# ESP32_LoRa_1_Channel_Gateway.net
KiCad netlist of a schematic drawn in EAGLE
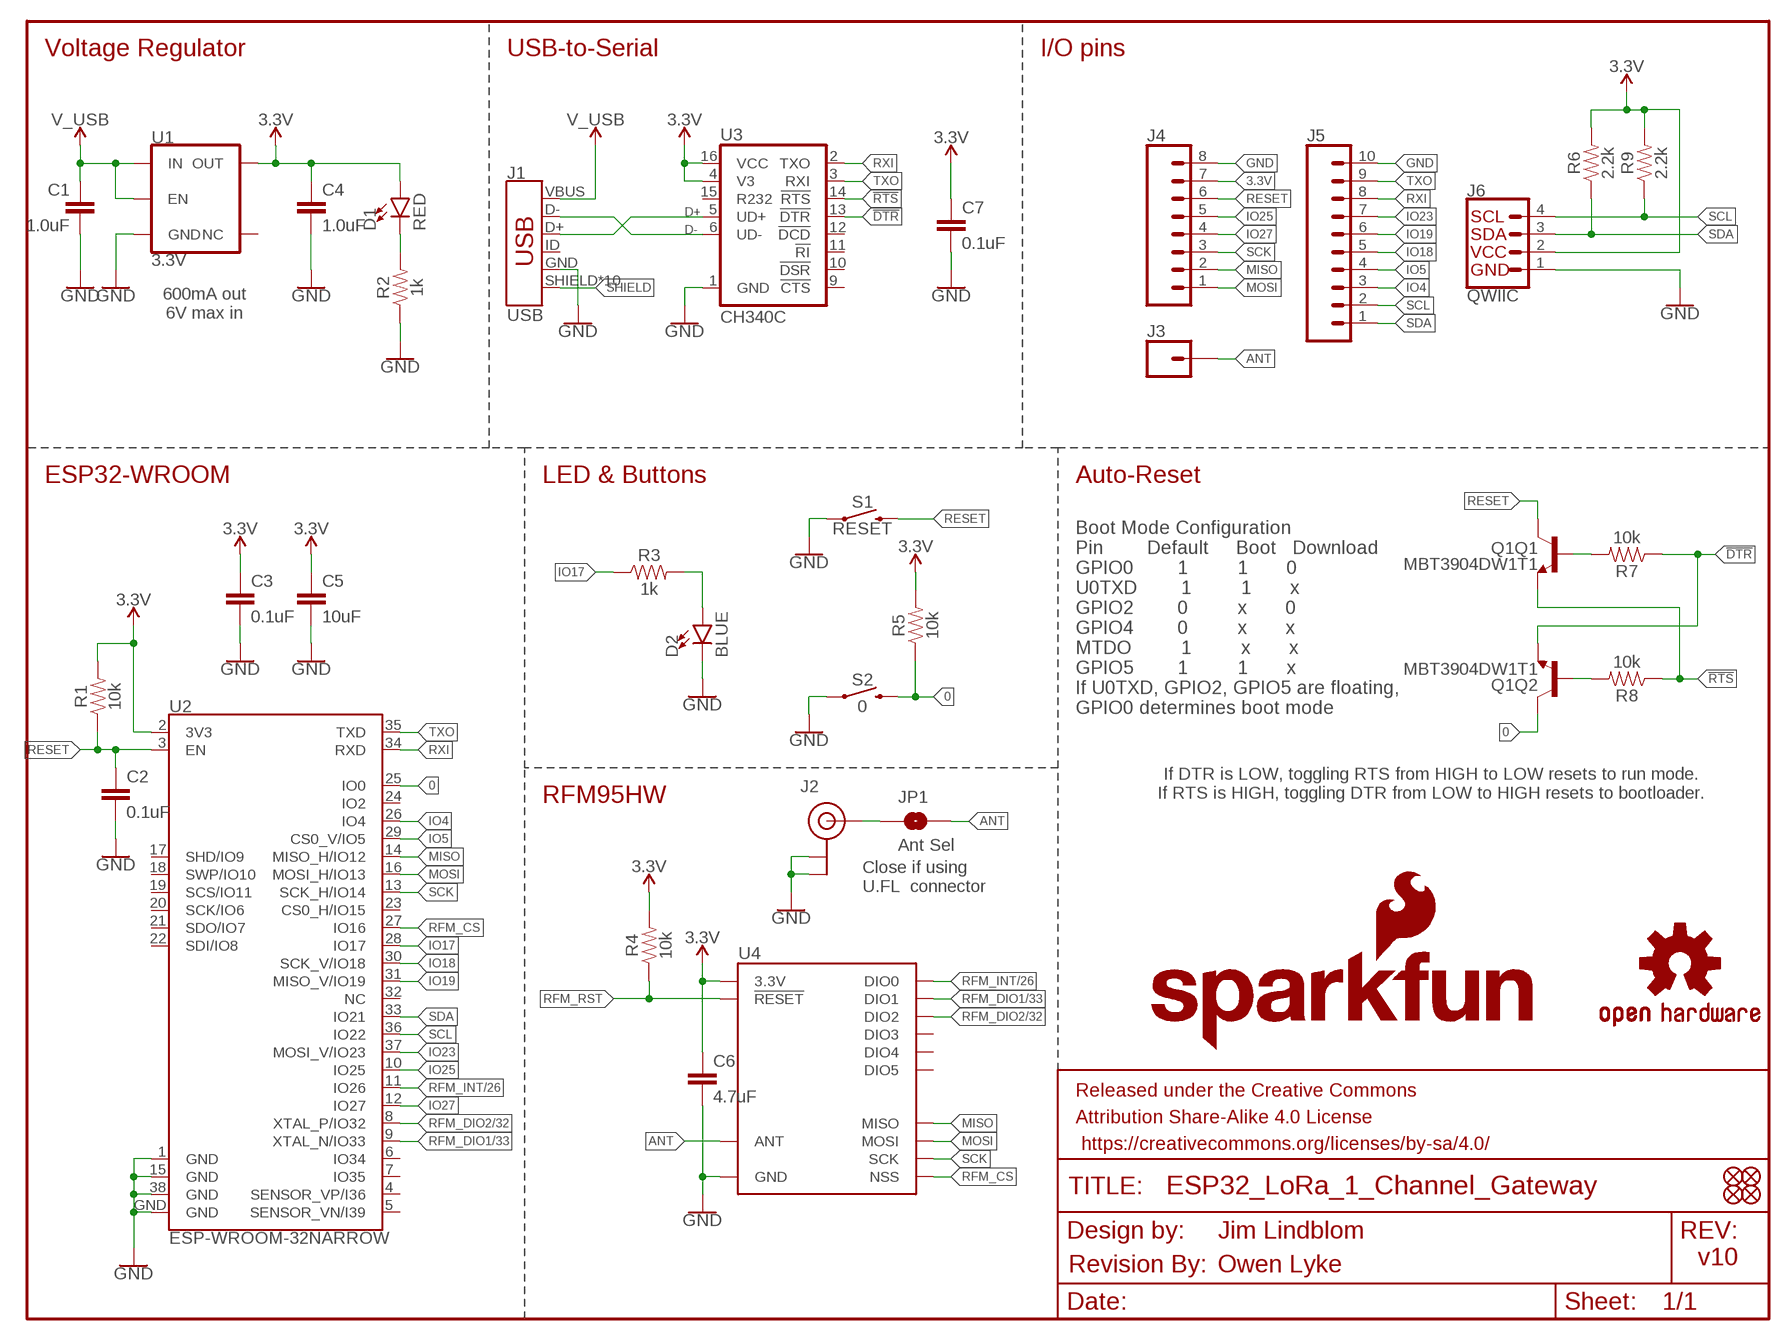
[diagram p0: schematic, sheet 1]

(export (version "E")
  (design (tool "Eeschema 10.0.6"))
  (components
    (comp (ref "C1")
      (value "1.0uF")
      (footprint "eagle-import:0603")
      (libsource (lib "eagle-import") (part "1.0UF-0603-16V-10%"))
    )
    (comp (ref "C2")
      (value "0.1uF")
      (footprint "eagle-import:0603")
      (libsource (lib "eagle-import") (part "0.1UF-0603-25V-(+80/-20%)"))
    )
    (comp (ref "C3")
      (value "0.1uF")
      (footprint "eagle-import:0603")
      (libsource (lib "eagle-import") (part "0.1UF-0603-25V-(+80/-20%)"))
    )
    (comp (ref "C4")
      (value "1.0uF")
      (footprint "eagle-import:0603")
      (libsource (lib "eagle-import") (part "1.0UF-0603-16V-10%"))
    )
    (comp (ref "C5")
      (value "10uF")
      (footprint "eagle-import:0603")
      (libsource (lib "eagle-import") (part "10UF-0603-6.3V-20%"))
    )
    (comp (ref "C6")
      (value "4.7uF")
      (footprint "eagle-import:0603")
      (libsource (lib "eagle-import") (part "4.7UF-0603-6.3V-(10%)"))
    )
    (comp (ref "C7")
      (value "0.1uF")
      (footprint "eagle-import:0603")
      (libsource (lib "eagle-import") (part "0.1UF-0603-25V-5%"))
    )
    (comp (ref "D1")
      (value "RED")
      (footprint "eagle-import:LED-0603")
      (libsource (lib "eagle-import") (part "LED-RED0603"))
    )
    (comp (ref "D2")
      (value "BLUE")
      (footprint "eagle-import:LED-0603")
      (libsource (lib "eagle-import") (part "LED-BLUE0603"))
    )
    (comp (ref "FD1")
      (value "FIDUCIAL1X2")
      (footprint "eagle-import:FIDUCIAL-1X2")
      (libsource (lib "eagle-import") (part "FIDUCIAL1X2"))
    )
    (comp (ref "FD2")
      (value "FIDUCIAL1X2")
      (footprint "eagle-import:FIDUCIAL-1X2")
      (libsource (lib "eagle-import") (part "FIDUCIAL1X2"))
    )
    (comp (ref "FD3")
      (value "FIDUCIAL1X2")
      (footprint "eagle-import:FIDUCIAL-1X2")
      (libsource (lib "eagle-import") (part "FIDUCIAL1X2"))
    )
    (comp (ref "FD4")
      (value "FIDUCIAL1X2")
      (footprint "eagle-import:FIDUCIAL-1X2")
      (libsource (lib "eagle-import") (part "FIDUCIAL1X2"))
    )
    (comp (ref "FRAME1")
      (value "FRAME-LETTER")
      (footprint "eagle-import:CREATIVE_COMMONS")
      (libsource (lib "eagle-import") (part "FRAME-LETTER"))
    )
    (comp (ref "J1")
      (value "USB")
      (footprint "eagle-import:USB-MICROB-PTH-MILL")
      (libsource (lib "eagle-import") (part "USB_MICRO-B_HALF_PTH_MILL"))
    )
    (comp (ref "J2")
      (value "U.FL")
      (footprint "eagle-import:U.FL")
      (libsource (lib "eagle-import") (part "U.FL"))
    )
    (comp (ref "J3")
      (value "CONN_01PTH_NO_SILK_YES_STOP")
      (footprint "eagle-import:1X01_NO_SILK")
      (libsource (lib "eagle-import") (part "CONN_01PTH_NO_SILK_YES_STOP"))
    )
    (comp (ref "J4")
      (value "CONN_08NO_SILK_FEMALE_PTH")
      (footprint "eagle-import:1X08_NO_SILK")
      (libsource (lib "eagle-import") (part "CONN_08NO_SILK_FEMALE_PTH"))
    )
    (comp (ref "J5")
      (value "CONN_10NO_SILK_PTH_FEMALE")
      (footprint "eagle-import:1X10_NO_SILK")
      (libsource (lib "eagle-import") (part "CONN_10NO_SILK_PTH_FEMALE"))
    )
    (comp (ref "J6")
      (value "QWIIC")
      (footprint "eagle-import:1X04_1MM_RA")
      (libsource (lib "eagle-import") (part "QWIIC_CONNECTORJS-1MM"))
    )
    (comp (ref "JP1")
      (value "Ant Sel")
      (footprint "eagle-import:SMT-JUMPER_2_NO_NO-SILK")
      (libsource (lib "eagle-import") (part "JUMPER-SMT_2_NO_NO-SILK"))
    )
    (comp (ref "LOGO1")
      (value "REVISION")
      (footprint "eagle-import:REVISION")
      (libsource (lib "eagle-import") (part "REVISION"))
    )
    (comp (ref "LOGO2")
      (value "SFE_LOGO_NAME_FLAME.1_INCH")
      (footprint "eagle-import:SFE_LOGO_NAME_FLAME_.1")
      (libsource (lib "eagle-import") (part "SFE_LOGO_NAME_FLAME.1_INCH"))
    )
    (comp (ref "LOGO3")
      (value "OSHW-LOGOS")
      (footprint "eagle-import:OSHW-LOGO-S")
      (libsource (lib "eagle-import") (part "OSHW-LOGOS"))
    )
    (comp (ref "Q1")
      (value "MBT3904DW1T1")
      (footprint "eagle-import:SC70-6")
      (libsource (lib "eagle-import") (part "TRANS_NPN_DUAL-MBT3904DW1T1"))
    )
    (comp (ref "R1")
      (value "10k")
      (footprint "eagle-import:0603")
      (libsource (lib "eagle-import") (part "10KOHM-0603-1/10W-1%"))
    )
    (comp (ref "R2")
      (value "1k")
      (footprint "eagle-import:0603")
      (libsource (lib "eagle-import") (part "1KOHM-0603-1/10W-1%"))
    )
    (comp (ref "R3")
      (value "1k")
      (footprint "eagle-import:0603")
      (libsource (lib "eagle-import") (part "1KOHM-0603-1/10W-1%"))
    )
    (comp (ref "R4")
      (value "10k")
      (footprint "eagle-import:0603")
      (libsource (lib "eagle-import") (part "10KOHM-0603-1/10W-1%"))
    )
    (comp (ref "R5")
      (value "10k")
      (footprint "eagle-import:0603")
      (libsource (lib "eagle-import") (part "10KOHM-0603-1/10W-1%"))
    )
    (comp (ref "R6")
      (value "2.2k")
      (footprint "eagle-import:0603")
      (libsource (lib "eagle-import") (part "2.2KOHM-0603-1/10W-1%"))
    )
    (comp (ref "R7")
      (value "10k")
      (footprint "eagle-import:0603")
      (libsource (lib "eagle-import") (part "10KOHM-0603-1/10W-1%"))
    )
    (comp (ref "R8")
      (value "10k")
      (footprint "eagle-import:0603")
      (libsource (lib "eagle-import") (part "10KOHM-0603-1/10W-1%"))
    )
    (comp (ref "R9")
      (value "2.2k")
      (footprint "eagle-import:0603")
      (libsource (lib "eagle-import") (part "2.2KOHM-0603-1/10W-1%"))
    )
    (comp (ref "S1")
      (value "RESET")
      (footprint "eagle-import:TACTILE_SWITCH_SMD_4.6X2.8MM")
      (libsource (lib "eagle-import") (part "MOMENTARY-SWITCH-SPST-SMD-4.6X2.8MM"))
    )
    (comp (ref "S2")
      (value "0")
      (footprint "eagle-import:TACTILE_SWITCH_SMD_4.6X2.8MM")
      (libsource (lib "eagle-import") (part "MOMENTARY-SWITCH-SPST-SMD-4.6X2.8MM"))
    )
    (comp (ref "U1")
      (value "3.3V")
      (footprint "eagle-import:SOT23-5")
      (libsource (lib "eagle-import") (part "V_REG_AP2112K-3.3V"))
    )
    (comp (ref "U2")
      (value "ESP-WROOM-32NARROW")
      (footprint "eagle-import:ESP-WROOM-32-NARROW")
      (libsource (lib "eagle-import") (part "ESP-WROOM-32NARROW"))
    )
    (comp (ref "U3")
      (value "CH340C")
      (footprint "eagle-import:SO016")
      (libsource (lib "eagle-import") (part "CH340C"))
    )
    (comp (ref "U4")
      (value "RFM95W")
      (footprint "eagle-import:RFM95_96_97_98W")
      (libsource (lib "eagle-import") (part "RFM95W"))
    )
  )
  (nets
    (net (code "1") (name "/D+") (class "Default")
      (node (ref "J1") (pin "D+") (pinfunction "D+_D+") (pintype "bidirectional"))
      (node (ref "U3") (pin "5") (pinfunction "UD+_5") (pintype "bidirectional"))
    )
    (net (code "2") (name "/D-") (class "Default")
      (node (ref "J1") (pin "D-") (pinfunction "D-_D-") (pintype "bidirectional"))
      (node (ref "U3") (pin "6") (pinfunction "UD-_6") (pintype "bidirectional"))
    )
    (net (code "3") (name "/~{DTR}") (class "Default")
      (node (ref "Q1") (pin "1") (pinfunction "E_1") (pintype "passive"))
      (node (ref "R7") (pin "1") (pinfunction "1_1") (pintype "passive"))
      (node (ref "U3") (pin "13") (pinfunction "~{DTR}_13") (pintype "bidirectional"))
    )
    (net (code "4") (name "/~{RTS}") (class "Default")
      (node (ref "Q1") (pin "4") (pinfunction "E_4") (pintype "passive"))
      (node (ref "R8") (pin "1") (pinfunction "1_1") (pintype "passive"))
      (node (ref "U3") (pin "14") (pinfunction "~{RTS}_14") (pintype "bidirectional"))
    )
    (net (code "5") (name "0") (class "Default")
      (node (ref "Q1") (pin "6") (pinfunction "C_6") (pintype "passive"))
      (node (ref "R5") (pin "1") (pinfunction "1_1") (pintype "passive"))
      (node (ref "S2") (pin "3") (pinfunction "2_3") (pintype "passive"))
      (node (ref "S2") (pin "4") (pinfunction "2_4") (pintype "passive"))
      (node (ref "U2") (pin "25") (pinfunction "IO0_25") (pintype "bidirectional"))
    )
    (net (code "6") (name "3.3V") (class "Default")
      (node (ref "C3") (pin "1") (pinfunction "1_1") (pintype "passive"))
      (node (ref "C4") (pin "1") (pinfunction "1_1") (pintype "passive"))
      (node (ref "C5") (pin "1") (pinfunction "1_1") (pintype "passive"))
      (node (ref "C6") (pin "1") (pinfunction "1_1") (pintype "passive"))
      (node (ref "C7") (pin "1") (pinfunction "1_1") (pintype "passive"))
      (node (ref "D1") (pin "A") (pinfunction "A_A") (pintype "passive"))
      (node (ref "J4") (pin "7") (pinfunction "7_7") (pintype "passive"))
      (node (ref "J6") (pin "2") (pinfunction "2_2") (pintype "power_in"))
      (node (ref "R1") (pin "2") (pinfunction "2_2") (pintype "passive"))
      (node (ref "R4") (pin "2") (pinfunction "2_2") (pintype "passive"))
      (node (ref "R5") (pin "2") (pinfunction "2_2") (pintype "passive"))
      (node (ref "R6") (pin "2") (pinfunction "2_2") (pintype "passive"))
      (node (ref "R9") (pin "2") (pinfunction "2_2") (pintype "passive"))
      (node (ref "U1") (pin "5") (pinfunction "OUT_5") (pintype "passive"))
      (node (ref "U2") (pin "2") (pinfunction "3V3_2") (pintype "bidirectional"))
      (node (ref "U3") (pin "16") (pinfunction "VCC_16") (pintype "bidirectional"))
      (node (ref "U3") (pin "4") (pinfunction "V3_4") (pintype "bidirectional"))
      (node (ref "U4") (pin "3.3V") (pinfunction "3.3V_3.3V") (pintype "bidirectional"))
    )
    (net (code "7") (name "ANT") (class "Default")
      (node (ref "J3") (pin "1") (pinfunction "1_1") (pintype "passive"))
      (node (ref "JP1") (pin "2") (pinfunction "2_2") (pintype "passive"))
      (node (ref "U4") (pin "ANT") (pinfunction "ANT_ANT") (pintype "bidirectional"))
    )
    (net (code "8") (name "GND") (class "Default")
      (node (ref "C1") (pin "2") (pinfunction "2_2") (pintype "passive"))
      (node (ref "C2") (pin "2") (pinfunction "2_2") (pintype "passive"))
      (node (ref "C3") (pin "2") (pinfunction "2_2") (pintype "passive"))
      (node (ref "C4") (pin "2") (pinfunction "2_2") (pintype "passive"))
      (node (ref "C5") (pin "2") (pinfunction "2_2") (pintype "passive"))
      (node (ref "C6") (pin "2") (pinfunction "2_2") (pintype "passive"))
      (node (ref "C7") (pin "2") (pinfunction "2_2") (pintype "passive"))
      (node (ref "D2") (pin "C") (pinfunction "C_C") (pintype "passive"))
      (node (ref "J1") (pin "GND") (pinfunction "GND_GND") (pintype "power_in"))
      (node (ref "J2") (pin "1") (pinfunction "GND_1") (pintype "bidirectional"))
      (node (ref "J2") (pin "2") (pinfunction "GND_2") (pintype "bidirectional"))
      (node (ref "J4") (pin "8") (pinfunction "8_8") (pintype "passive"))
      (node (ref "J5") (pin "10") (pinfunction "10_10") (pintype "passive"))
      (node (ref "J6") (pin "1") (pinfunction "1_1") (pintype "power_in"))
      (node (ref "R2") (pin "1") (pinfunction "1_1") (pintype "passive"))
      (node (ref "S1") (pin "1") (pinfunction "1_1") (pintype "passive"))
      (node (ref "S1") (pin "2") (pinfunction "1_2") (pintype "passive"))
      (node (ref "S2") (pin "1") (pinfunction "1_1") (pintype "passive"))
      (node (ref "S2") (pin "2") (pinfunction "1_2") (pintype "passive"))
      (node (ref "U1") (pin "2") (pinfunction "GND_2") (pintype "input"))
      (node (ref "U2") (pin "1") (pinfunction "GND_1") (pintype "bidirectional"))
      (node (ref "U2") (pin "15") (pinfunction "GND_15") (pintype "bidirectional"))
      (node (ref "U2") (pin "38") (pinfunction "GND_38") (pintype "bidirectional"))
      (node (ref "U2") (pin "GND") (pinfunction "GND_GND") (pintype "bidirectional"))
      (node (ref "U3") (pin "1") (pinfunction "GND_1") (pintype "bidirectional"))
      (node (ref "U4") (pin "GND@1") (pinfunction "GND_GND@1") (pintype "bidirectional"))
      (node (ref "U4") (pin "GND@2") (pinfunction "GND_GND@2") (pintype "bidirectional"))
      (node (ref "U4") (pin "GND@3") (pinfunction "GND_GND@3") (pintype "bidirectional"))
    )
    (net (code "9") (name "IO4") (class "Default")
      (node (ref "J5") (pin "3") (pinfunction "3_3") (pintype "passive"))
      (node (ref "U2") (pin "26") (pinfunction "IO4_26") (pintype "bidirectional"))
    )
    (net (code "10") (name "IO5") (class "Default")
      (node (ref "J5") (pin "4") (pinfunction "4_4") (pintype "passive"))
      (node (ref "U2") (pin "29") (pinfunction "CS0_V/IO5_29") (pintype "bidirectional"))
    )
    (net (code "11") (name "IO17") (class "Default")
      (node (ref "R3") (pin "1") (pinfunction "1_1") (pintype "passive"))
      (node (ref "U2") (pin "28") (pinfunction "IO17_28") (pintype "bidirectional"))
    )
    (net (code "12") (name "IO18") (class "Default")
      (node (ref "J5") (pin "5") (pinfunction "5_5") (pintype "passive"))
      (node (ref "U2") (pin "30") (pinfunction "SCK_V/IO18_30") (pintype "bidirectional"))
    )
    (net (code "13") (name "IO19") (class "Default")
      (node (ref "J5") (pin "6") (pinfunction "6_6") (pintype "passive"))
      (node (ref "U2") (pin "31") (pinfunction "MISO_V/IO19_31") (pintype "bidirectional"))
    )
    (net (code "14") (name "IO23") (class "Default")
      (node (ref "J5") (pin "7") (pinfunction "7_7") (pintype "passive"))
      (node (ref "U2") (pin "37") (pinfunction "MOSI_V/IO23_37") (pintype "bidirectional"))
    )
    (net (code "15") (name "IO25") (class "Default")
      (node (ref "J4") (pin "5") (pinfunction "5_5") (pintype "passive"))
      (node (ref "U2") (pin "10") (pinfunction "IO25_10") (pintype "bidirectional"))
    )
    (net (code "16") (name "IO27") (class "Default")
      (node (ref "J4") (pin "4") (pinfunction "4_4") (pintype "passive"))
      (node (ref "U2") (pin "12") (pinfunction "IO27_12") (pintype "bidirectional"))
    )
    (net (code "17") (name "MISO") (class "Default")
      (node (ref "J4") (pin "2") (pinfunction "2_2") (pintype "passive"))
      (node (ref "U2") (pin "14") (pinfunction "MISO_H/IO12_14") (pintype "bidirectional"))
      (node (ref "U4") (pin "MISO") (pinfunction "MISO_MISO") (pintype "bidirectional"))
    )
    (net (code "18") (name "MOSI") (class "Default")
      (node (ref "J4") (pin "1") (pinfunction "1_1") (pintype "passive"))
      (node (ref "U2") (pin "16") (pinfunction "MOSI_H/IO13_16") (pintype "bidirectional"))
      (node (ref "U4") (pin "MOSI") (pinfunction "MOSI_MOSI") (pintype "bidirectional"))
    )
    (net (code "19") (name "Net-(D1-PadC)") (class "Default")
      (node (ref "D1") (pin "C") (pinfunction "C_C") (pintype "passive"))
      (node (ref "R2") (pin "2") (pinfunction "2_2") (pintype "passive"))
    )
    (net (code "20") (name "Net-(D2-PadA)") (class "Default")
      (node (ref "D2") (pin "A") (pinfunction "A_A") (pintype "passive"))
      (node (ref "R3") (pin "2") (pinfunction "2_2") (pintype "passive"))
    )
    (net (code "21") (name "Net-(J2-SIGNAL)") (class "Default")
      (node (ref "J2") (pin "FEED") (pinfunction "SIGNAL_FEED") (pintype "bidirectional"))
      (node (ref "JP1") (pin "1") (pinfunction "1_1") (pintype "passive"))
    )
    (net (code "22") (name "Net-(Q1A-B)") (class "Default")
      (node (ref "Q1") (pin "5") (pinfunction "B_5") (pintype "passive"))
      (node (ref "R7") (pin "2") (pinfunction "2_2") (pintype "passive"))
    )
    (net (code "23") (name "Net-(Q1B-B)") (class "Default")
      (node (ref "Q1") (pin "2") (pinfunction "B_2") (pintype "passive"))
      (node (ref "R8") (pin "2") (pinfunction "2_2") (pintype "passive"))
    )
    (net (code "24") (name "RESET") (class "Default")
      (node (ref "C2") (pin "1") (pinfunction "1_1") (pintype "passive"))
      (node (ref "J4") (pin "6") (pinfunction "6_6") (pintype "passive"))
      (node (ref "Q1") (pin "3") (pinfunction "C_3") (pintype "passive"))
      (node (ref "R1") (pin "1") (pinfunction "1_1") (pintype "passive"))
      (node (ref "S1") (pin "3") (pinfunction "2_3") (pintype "passive"))
      (node (ref "S1") (pin "4") (pinfunction "2_4") (pintype "passive"))
      (node (ref "U2") (pin "3") (pinfunction "EN_3") (pintype "bidirectional"))
    )
    (net (code "25") (name "RFM_CS") (class "Default")
      (node (ref "U2") (pin "27") (pinfunction "IO16_27") (pintype "bidirectional"))
      (node (ref "U4") (pin "NSS") (pinfunction "NSS_NSS") (pintype "bidirectional"))
    )
    (net (code "26") (name "RFM_DIO1{slash}33") (class "Default")
      (node (ref "U2") (pin "9") (pinfunction "XTAL_N/IO33_9") (pintype "bidirectional"))
      (node (ref "U4") (pin "DIO1") (pinfunction "DIO1_DIO1") (pintype "bidirectional"))
    )
    (net (code "27") (name "RFM_DIO2{slash}32") (class "Default")
      (node (ref "U2") (pin "8") (pinfunction "XTAL_P/IO32_8") (pintype "bidirectional"))
      (node (ref "U4") (pin "DIO2") (pinfunction "DIO2_DIO2") (pintype "bidirectional"))
    )
    (net (code "28") (name "RFM_INT{slash}26") (class "Default")
      (node (ref "U2") (pin "11") (pinfunction "IO26_11") (pintype "bidirectional"))
      (node (ref "U4") (pin "DIO0") (pinfunction "DIO0_DIO0") (pintype "bidirectional"))
    )
    (net (code "29") (name "RFM_RST") (class "Default")
      (node (ref "R4") (pin "1") (pinfunction "1_1") (pintype "passive"))
      (node (ref "U4") (pin "!RESET") (pinfunction "~{RESET}_!RESET") (pintype "bidirectional"))
    )
    (net (code "30") (name "RXI") (class "Default")
      (node (ref "J5") (pin "8") (pinfunction "8_8") (pintype "passive"))
      (node (ref "U2") (pin "34") (pinfunction "RXD_34") (pintype "bidirectional"))
      (node (ref "U3") (pin "2") (pinfunction "TXO_2") (pintype "bidirectional"))
    )
    (net (code "31") (name "SCK") (class "Default")
      (node (ref "J4") (pin "3") (pinfunction "3_3") (pintype "passive"))
      (node (ref "U2") (pin "13") (pinfunction "SCK_H/IO14_13") (pintype "bidirectional"))
      (node (ref "U4") (pin "SCK") (pinfunction "SCK_SCK") (pintype "bidirectional"))
    )
    (net (code "32") (name "SCL") (class "Default")
      (node (ref "J5") (pin "2") (pinfunction "2_2") (pintype "passive"))
      (node (ref "J6") (pin "4") (pinfunction "4_4") (pintype "passive"))
      (node (ref "R9") (pin "1") (pinfunction "1_1") (pintype "passive"))
      (node (ref "U2") (pin "36") (pinfunction "IO22_36") (pintype "bidirectional"))
    )
    (net (code "33") (name "SDA") (class "Default")
      (node (ref "J5") (pin "1") (pinfunction "1_1") (pintype "passive"))
      (node (ref "J6") (pin "3") (pinfunction "3_3") (pintype "passive"))
      (node (ref "R6") (pin "1") (pinfunction "1_1") (pintype "passive"))
      (node (ref "U2") (pin "33") (pinfunction "IO21_33") (pintype "bidirectional"))
    )
    (net (code "34") (name "SHIELD") (class "Default")
      (node (ref "J1") (pin "SHIELD") (pinfunction "SHIELD_SHIELD") (pintype "bidirectional"))
      (node (ref "J1") (pin "SHIELD10") (pinfunction "SHIELD_SHIELD10") (pintype "bidirectional"))
      (node (ref "J1") (pin "SHIELD2") (pinfunction "SHIELD_SHIELD2") (pintype "bidirectional"))
      (node (ref "J1") (pin "SHIELD3") (pinfunction "SHIELD_SHIELD3") (pintype "bidirectional"))
      (node (ref "J1") (pin "SHIELD4") (pinfunction "SHIELD_SHIELD4") (pintype "bidirectional"))
      (node (ref "J1") (pin "SHIELD5") (pinfunction "SHIELD_SHIELD5") (pintype "bidirectional"))
      (node (ref "J1") (pin "SHIELD6") (pinfunction "SHIELD_SHIELD6") (pintype "bidirectional"))
      (node (ref "J1") (pin "SHIELD7") (pinfunction "SHIELD_SHIELD7") (pintype "bidirectional"))
      (node (ref "J1") (pin "SHIELD8") (pinfunction "SHIELD_SHIELD8") (pintype "bidirectional"))
      (node (ref "J1") (pin "SHIELD9") (pinfunction "SHIELD_SHIELD9") (pintype "bidirectional"))
    )
    (net (code "35") (name "TXO") (class "Default")
      (node (ref "J5") (pin "9") (pinfunction "9_9") (pintype "passive"))
      (node (ref "U2") (pin "35") (pinfunction "TXD_35") (pintype "bidirectional"))
      (node (ref "U3") (pin "3") (pinfunction "RXI_3") (pintype "bidirectional"))
    )
    (net (code "36") (name "V_USB") (class "Default")
      (node (ref "C1") (pin "1") (pinfunction "1_1") (pintype "passive"))
      (node (ref "J1") (pin "VBUS") (pinfunction "VBUS_VBUS") (pintype "power_in"))
      (node (ref "U1") (pin "1") (pinfunction "IN_1") (pintype "input"))
      (node (ref "U1") (pin "3") (pinfunction "EN_3") (pintype "input"))
    )
    (net (code "37") (name "unconnected-(J1-PadID)") (class "Default")
      (node (ref "J1") (pin "ID") (pinfunction "ID_ID") (pintype "bidirectional"))
    )
    (net (code "38") (name "unconnected-(U1-NC-Pad4)") (class "Default")
      (node (ref "U1") (pin "4") (pinfunction "NC_4") (pintype "no_connect"))
    )
    (net (code "39") (name "unconnected-(U2-CS0_H{slash}IO15-Pad23)") (class "Default")
      (node (ref "U2") (pin "23") (pinfunction "CS0_H/IO15_23") (pintype "bidirectional"))
    )
    (net (code "40") (name "unconnected-(U2-IO2-Pad24)") (class "Default")
      (node (ref "U2") (pin "24") (pinfunction "IO2_24") (pintype "bidirectional"))
    )
    (net (code "41") (name "unconnected-(U2-IO34-Pad6)") (class "Default")
      (node (ref "U2") (pin "6") (pinfunction "IO34_6") (pintype "bidirectional"))
    )
    (net (code "42") (name "unconnected-(U2-IO35-Pad7)") (class "Default")
      (node (ref "U2") (pin "7") (pinfunction "IO35_7") (pintype "bidirectional"))
    )
    (net (code "43") (name "unconnected-(U2-NC-Pad32)") (class "Default")
      (node (ref "U2") (pin "32") (pinfunction "NC_32") (pintype "bidirectional"))
    )
    (net (code "44") (name "unconnected-(U2-SCK{slash}IO6-Pad20)") (class "Default")
      (node (ref "U2") (pin "20") (pinfunction "SCK/IO6_20") (pintype "bidirectional"))
    )
    (net (code "45") (name "unconnected-(U2-SCS{slash}IO11-Pad19)") (class "Default")
      (node (ref "U2") (pin "19") (pinfunction "SCS/IO11_19") (pintype "bidirectional"))
    )
    (net (code "46") (name "unconnected-(U2-SDI{slash}IO8-Pad22)") (class "Default")
      (node (ref "U2") (pin "22") (pinfunction "SDI/IO8_22") (pintype "bidirectional"))
    )
    (net (code "47") (name "unconnected-(U2-SDO{slash}IO7-Pad21)") (class "Default")
      (node (ref "U2") (pin "21") (pinfunction "SDO/IO7_21") (pintype "bidirectional"))
    )
    (net (code "48") (name "unconnected-(U2-SENSOR_VN{slash}I39-Pad5)") (class "Default")
      (node (ref "U2") (pin "5") (pinfunction "SENSOR_VN/I39_5") (pintype "bidirectional"))
    )
    (net (code "49") (name "unconnected-(U2-SENSOR_VP{slash}I36-Pad4)") (class "Default")
      (node (ref "U2") (pin "4") (pinfunction "SENSOR_VP/I36_4") (pintype "bidirectional"))
    )
    (net (code "50") (name "unconnected-(U2-SHD{slash}IO9-Pad17)") (class "Default")
      (node (ref "U2") (pin "17") (pinfunction "SHD/IO9_17") (pintype "bidirectional"))
    )
    (net (code "51") (name "unconnected-(U2-SWP{slash}IO10-Pad18)") (class "Default")
      (node (ref "U2") (pin "18") (pinfunction "SWP/IO10_18") (pintype "bidirectional"))
    )
    (net (code "52") (name "unconnected-(U3-R232-Pad15)") (class "Default")
      (node (ref "U3") (pin "15") (pinfunction "R232_15") (pintype "bidirectional"))
    )
    (net (code "53") (name "unconnected-(U3-~{CTS}-Pad9)") (class "Default")
      (node (ref "U3") (pin "9") (pinfunction "~{CTS}_9") (pintype "bidirectional"))
    )
    (net (code "54") (name "unconnected-(U3-~{DCD}-Pad12)") (class "Default")
      (node (ref "U3") (pin "12") (pinfunction "~{DCD}_12") (pintype "bidirectional"))
    )
    (net (code "55") (name "unconnected-(U3-~{DSR}-Pad10)") (class "Default")
      (node (ref "U3") (pin "10") (pinfunction "~{DSR}_10") (pintype "bidirectional"))
    )
    (net (code "56") (name "unconnected-(U3-~{RI}-Pad11)") (class "Default")
      (node (ref "U3") (pin "11") (pinfunction "~{RI}_11") (pintype "bidirectional"))
    )
    (net (code "57") (name "unconnected-(U4-PadDIO3)") (class "Default")
      (node (ref "U4") (pin "DIO3") (pinfunction "DIO3_DIO3") (pintype "bidirectional"))
    )
    (net (code "58") (name "unconnected-(U4-PadDIO4)") (class "Default")
      (node (ref "U4") (pin "DIO4") (pinfunction "DIO4_DIO4") (pintype "bidirectional"))
    )
    (net (code "59") (name "unconnected-(U4-PadDIO5)") (class "Default")
      (node (ref "U4") (pin "DIO5") (pinfunction "DIO5_DIO5") (pintype "bidirectional"))
    )
  )
)
